# Rain_Module_v2_SCH.net
KiCad netlist of a schematic drawn in Altium Designer
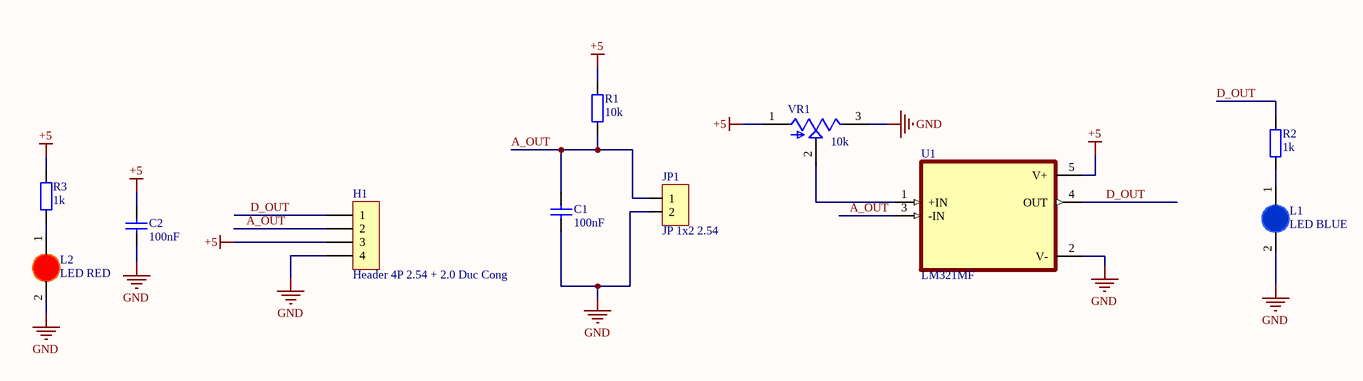
[diagram p0: Rain Module_v2_SCH.SchDoc]

(export (version "E")
  (design (tool "Eeschema 10.0.6"))
  (components
    (comp (ref "C1")
      (value "100nF")
      (footprint "tu 0603")
      (description "Dán")
      (libsource (lib "namnt_Lib") (part "Tu 0603 104 50V 10%"))
    )
    (comp (ref "C2")
      (value "100nF")
      (footprint "tu 0603")
      (description "Dán")
      (libsource (lib "namnt_Lib") (part "Tu 0603 104 50V 10%"))
    )
    (comp (ref "H1")
      (value "Header 4P 2.54 + 2.0 Duc Cong")
      (footprint "Header 4P DC 2.54 + 2.0")
      (description "Cắm")
      (libsource (lib "namnt_Lib") (part "Header 4P 2.54 + 2.0 Duc Cong"))
    )
    (comp (ref "JP1")
      (value "JP 1x2 2.54")
      (footprint "JP 1x2 DC")
      (description "Cắm")
      (libsource (lib "namnt_Lib") (part "JP 1x2 2.54 Duc Cong"))
    )
    (comp (ref "L1")
      (value "LED BLUE")
      (footprint "LED-0805-Blue")
      (description "Dán")
      (libsource (lib "namnt_Lib") (part "LED 0805 Xanh Duong"))
    )
    (comp (ref "L2")
      (value "LED RED")
      (footprint "LED-0805-Red")
      (description "Dán")
      (libsource (lib "namnt_Lib") (part "LED 0805 Do"))
    )
    (comp (ref "R1")
      (value "10k")
      (footprint "tro smd 0603")
      (description "Dán")
      (libsource (lib "namnt_Lib") (part "Tro 0603 1% 10k"))
    )
    (comp (ref "R2")
      (value "1k")
      (footprint "tro smd 0603")
      (description "Dán")
      (libsource (lib "namnt_Lib") (part "Tro 0603 1% 1k"))
    )
    (comp (ref "R3")
      (value "1k")
      (footprint "tro smd 0603")
      (description "Dán")
      (libsource (lib "namnt_Lib") (part "Tro 0603 1% 1k"))
    )
    (comp (ref "U1")
      (value "LM321MF")
      (footprint "SOT95P280X145-5N")
      (description "Low Power Single Op Amp 5-SOT-23 -40 to 85")
      (fields (field (name "MF") "Texas Instruments"))
      (libsource (lib "namnt_Lib") (part "LM321MF"))
    )
    (comp (ref "VR1")
      (value "10k")
      (footprint "TRIM_3362P-1-102")
      (description "TRIMMER - 1/4in SQ ST CERMET ¦ Bourns 3362P-1-102")
      (fields (field (name "MF") "Bourns") (field (name "MP") "3362P-1-102"))
      (libsource (lib "namnt_Lib") (part "Bien tro vuong"))
    )
  )
  (nets
    (net (code "1") (name "+5") (class "Default")
      (node (ref "C2") (pin "1") (pinfunction "1_1") (pintype "passive"))
      (node (ref "H1") (pin "3") (pinfunction "3_3") (pintype "passive"))
      (node (ref "R1") (pin "2") (pinfunction "2_2") (pintype "passive"))
      (node (ref "R3") (pin "2") (pinfunction "2_2") (pintype "passive"))
      (node (ref "U1") (pin "5") (pinfunction "V+_5") (pintype "power_in"))
      (node (ref "VR1") (pin "1") (pinfunction "CCW_1") (pintype "passive"))
    )
    (net (code "2") (name "/A_OUT") (class "Default")
      (node (ref "C1") (pin "1") (pinfunction "1_1") (pintype "passive"))
      (node (ref "H1") (pin "2") (pinfunction "2_2") (pintype "passive"))
      (node (ref "JP1") (pin "1") (pinfunction "1_1") (pintype "passive"))
      (node (ref "R1") (pin "1") (pinfunction "1_1") (pintype "passive"))
      (node (ref "U1") (pin "3") (pinfunction "-IN_3") (pintype "input"))
    )
    (net (code "3") (name "/D_OUT") (class "Default")
      (node (ref "H1") (pin "1") (pinfunction "1_1") (pintype "passive"))
      (node (ref "R2") (pin "2") (pinfunction "2_2") (pintype "passive"))
      (node (ref "U1") (pin "4") (pinfunction "OUT_4") (pintype "output"))
    )
    (net (code "4") (name "GND") (class "Default")
      (node (ref "C1") (pin "2") (pinfunction "2_2") (pintype "passive"))
      (node (ref "C2") (pin "2") (pinfunction "2_2") (pintype "passive"))
      (node (ref "H1") (pin "4") (pinfunction "4_4") (pintype "passive"))
      (node (ref "JP1") (pin "2") (pinfunction "2_2") (pintype "passive"))
      (node (ref "L1") (pin "2") (pinfunction "K_2") (pintype "passive"))
      (node (ref "L2") (pin "2") (pinfunction "K_2") (pintype "passive"))
      (node (ref "U1") (pin "2") (pinfunction "V-_2") (pintype "power_in"))
      (node (ref "VR1") (pin "3") (pinfunction "CW_3") (pintype "passive"))
    )
    (net (code "5") (name "Net-(L1-A)") (class "Default")
      (node (ref "L1") (pin "1") (pinfunction "A_1") (pintype "passive"))
      (node (ref "R2") (pin "1") (pinfunction "1_1") (pintype "passive"))
    )
    (net (code "6") (name "Net-(L2-A)") (class "Default")
      (node (ref "L2") (pin "1") (pinfunction "A_1") (pintype "passive"))
      (node (ref "R3") (pin "1") (pinfunction "1_1") (pintype "passive"))
    )
    (net (code "7") (name "Net-(U1-+IN)") (class "Default")
      (node (ref "U1") (pin "1") (pinfunction "+IN_1") (pintype "input"))
      (node (ref "VR1") (pin "2") (pinfunction "WIPER_2") (pintype "passive"))
    )
  )
)
